# extension_board.net
KiCad netlist of a schematic drawn in Altium Designer
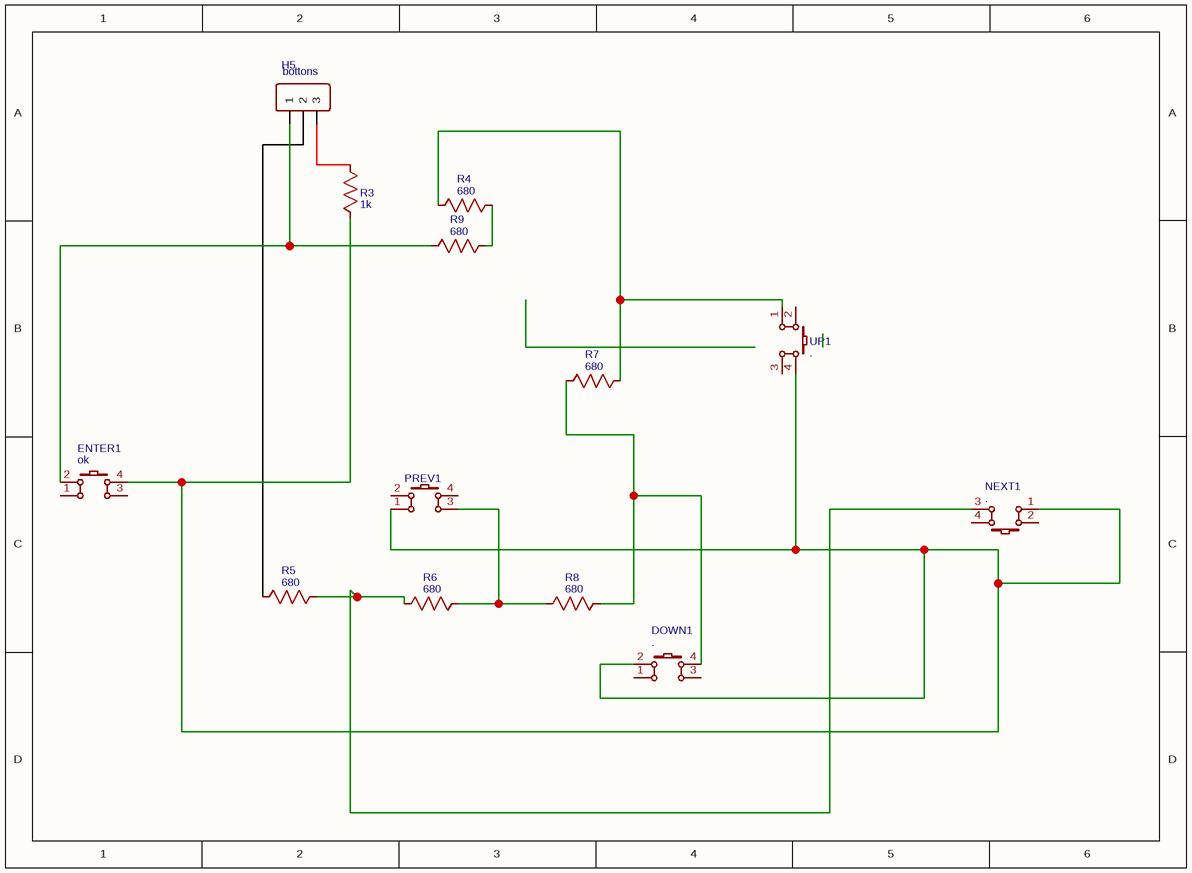
[diagram p0: extension board.schdoc]

(export (version "E")
  (design (tool "Eeschema 10.0.6"))
  (components
    (comp (ref "DOWN1")
      (value ".")
      (fields
        (field (name "BOM_SUPPLIER PART") "C136684")
        (field (name "BOM_MANUFACTURER PART") "K2-1102DP-E4SW-04")
        (field (name "CONTRIBUTOR") "LCEDA_Lib")
      )
      (libsource (lib "altium-import") (part "root_0_._"))
    )
    (comp (ref "ENTER1")
      (value "ok")
      (fields
        (field (name "BOM_SUPPLIER PART") "C136684")
        (field (name "BOM_MANUFACTURER PART") "K2-1102DP-E4SW-04")
        (field (name "CONTRIBUTOR") "LCEDA_Lib")
      )
      (libsource (lib "altium-import") (part "root_0_ok_"))
    )
    (comp (ref "H5")
      (value "bottons")
      (fields (field (name "BOM_SUPPLIER PART") "C146690") (field (name "CONTRIBUTOR") "LCEDA_Lib"))
      (libsource (lib "altium-import") (part "root_1_bottons_"))
    )
    (comp (ref "NEXT1")
      (value ".")
      (fields
        (field (name "BOM_SUPPLIER PART") "C136684")
        (field (name "BOM_MANUFACTURER PART") "K2-1102DP-E4SW-04")
        (field (name "CONTRIBUTOR") "LCEDA_Lib")
      )
      (libsource (lib "altium-import") (part "root_2_._"))
    )
    (comp (ref "PREV1")
      (value ".")
      (fields
        (field (name "BOM_SUPPLIER PART") "C136684")
        (field (name "BOM_MANUFACTURER PART") "K2-1102DP-E4SW-04")
        (field (name "CONTRIBUTOR") "LCEDA_Lib")
      )
      (libsource (lib "altium-import") (part "root_0_._"))
    )
    (comp (ref "R3")
      (value "1k")
      (fields (field (name "CONTRIBUTOR") "LCEDA_Lib"))
      (libsource (lib "altium-import") (part "root_1_1k_"))
    )
    (comp (ref "R4")
      (value "680")
      (fields (field (name "CONTRIBUTOR") "LCEDA_Lib"))
      (libsource (lib "altium-import") (part "root_0_680_"))
    )
    (comp (ref "R5")
      (value "680")
      (fields (field (name "CONTRIBUTOR") "LCEDA_Lib"))
      (libsource (lib "altium-import") (part "root_0_680_"))
    )
    (comp (ref "R6")
      (value "680")
      (fields (field (name "CONTRIBUTOR") "LCEDA_Lib"))
      (libsource (lib "altium-import") (part "root_0_680_"))
    )
    (comp (ref "R7")
      (value "680")
      (fields (field (name "CONTRIBUTOR") "LCEDA_Lib"))
      (libsource (lib "altium-import") (part "root_0_680_"))
    )
    (comp (ref "R8")
      (value "680")
      (fields (field (name "CONTRIBUTOR") "LCEDA_Lib"))
      (libsource (lib "altium-import") (part "root_0_680_"))
    )
    (comp (ref "R9")
      (value "680")
      (fields (field (name "CONTRIBUTOR") "LCEDA_Lib"))
      (libsource (lib "altium-import") (part "root_0_680_"))
    )
    (comp (ref "UP1")
      (value ".")
      (fields
        (field (name "BOM_SUPPLIER PART") "C136684")
        (field (name "BOM_MANUFACTURER PART") "K2-1102DP-E4SW-04")
        (field (name "CONTRIBUTOR") "LCEDA_Lib")
      )
      (libsource (lib "altium-import") (part "root_3_._"))
    )
  )
  (nets
    (net (code "1") (name "Net-(DOWN1-Pad2)") (class "Default")
      (node (ref "DOWN1") (pin "2") (pinfunction "2_2") (pintype "passive"))
      (node (ref "ENTER1") (pin "4") (pinfunction "4_4") (pintype "passive"))
      (node (ref "NEXT1") (pin "1") (pinfunction "1_1") (pintype "passive"))
      (node (ref "PREV1") (pin "1") (pinfunction "1_1") (pintype "passive"))
      (node (ref "R3") (pin "1") (pinfunction "1_1") (pintype "passive"))
      (node (ref "UP1") (pin "4") (pinfunction "4_4") (pintype "passive"))
    )
    (net (code "2") (name "Net-(DOWN1-Pad4)") (class "Default")
      (node (ref "DOWN1") (pin "4") (pinfunction "4_4") (pintype "passive"))
      (node (ref "R7") (pin "1") (pinfunction "1_1") (pintype "passive"))
      (node (ref "R8") (pin "2") (pinfunction "2_2") (pintype "passive"))
    )
    (net (code "3") (name "Net-(ENTER1-Pad2)") (class "Default")
      (node (ref "ENTER1") (pin "2") (pinfunction "2_2") (pintype "passive"))
      (node (ref "H5") (pin "1") (pinfunction "1_1") (pintype "passive"))
      (node (ref "R9") (pin "1") (pinfunction "1_1") (pintype "passive"))
    )
    (net (code "4") (name "Net-(H5-Pad2)") (class "Default")
      (node (ref "H5") (pin "2") (pinfunction "2_2") (pintype "passive"))
      (node (ref "R5") (pin "1") (pinfunction "1_1") (pintype "passive"))
    )
    (net (code "5") (name "Net-(H5-Pad3)") (class "Default")
      (node (ref "H5") (pin "3") (pinfunction "3_3") (pintype "passive"))
      (node (ref "R3") (pin "2") (pinfunction "2_2") (pintype "passive"))
    )
    (net (code "6") (name "Net-(NEXT1-Pad3)") (class "Default")
      (node (ref "NEXT1") (pin "3") (pinfunction "3_3") (pintype "passive"))
      (node (ref "R5") (pin "2") (pinfunction "2_2") (pintype "passive"))
      (node (ref "R6") (pin "1") (pinfunction "1_1") (pintype "passive"))
    )
    (net (code "7") (name "Net-(PREV1-Pad3)") (class "Default")
      (node (ref "PREV1") (pin "3") (pinfunction "3_3") (pintype "passive"))
      (node (ref "R6") (pin "2") (pinfunction "2_2") (pintype "passive"))
      (node (ref "R8") (pin "1") (pinfunction "1_1") (pintype "passive"))
    )
    (net (code "8") (name "Net-(R4-Pad1)") (class "Default")
      (node (ref "R4") (pin "1") (pinfunction "1_1") (pintype "passive"))
      (node (ref "R7") (pin "2") (pinfunction "2_2") (pintype "passive"))
      (node (ref "UP1") (pin "1") (pinfunction "1_1") (pintype "passive"))
    )
    (net (code "9") (name "Net-(R4-Pad2)") (class "Default")
      (node (ref "R4") (pin "2") (pinfunction "2_2") (pintype "passive"))
      (node (ref "R9") (pin "2") (pinfunction "2_2") (pintype "passive"))
    )
    (net (code "10") (name "unconnected-(DOWN1-Pad1)") (class "Default")
      (node (ref "DOWN1") (pin "1") (pinfunction "1_1") (pintype "passive"))
    )
    (net (code "11") (name "unconnected-(DOWN1-Pad3)") (class "Default")
      (node (ref "DOWN1") (pin "3") (pinfunction "3_3") (pintype "passive"))
    )
    (net (code "12") (name "unconnected-(ENTER1-Pad1)") (class "Default")
      (node (ref "ENTER1") (pin "1") (pinfunction "1_1") (pintype "passive"))
    )
    (net (code "13") (name "unconnected-(ENTER1-Pad3)") (class "Default")
      (node (ref "ENTER1") (pin "3") (pinfunction "3_3") (pintype "passive"))
    )
    (net (code "14") (name "unconnected-(NEXT1-Pad2)") (class "Default")
      (node (ref "NEXT1") (pin "2") (pinfunction "2_2") (pintype "passive"))
    )
    (net (code "15") (name "unconnected-(NEXT1-Pad4)") (class "Default")
      (node (ref "NEXT1") (pin "4") (pinfunction "4_4") (pintype "passive"))
    )
    (net (code "16") (name "unconnected-(PREV1-Pad2)") (class "Default")
      (node (ref "PREV1") (pin "2") (pinfunction "2_2") (pintype "passive"))
    )
    (net (code "17") (name "unconnected-(PREV1-Pad4)") (class "Default")
      (node (ref "PREV1") (pin "4") (pinfunction "4_4") (pintype "passive"))
    )
    (net (code "18") (name "unconnected-(UP1-Pad2)") (class "Default")
      (node (ref "UP1") (pin "2") (pinfunction "2_2") (pintype "passive"))
    )
    (net (code "19") (name "unconnected-(UP1-Pad3)") (class "Default")
      (node (ref "UP1") (pin "3") (pinfunction "3_3") (pintype "passive"))
    )
  )
)
